# Day0_Samuel_Siahaan_13214088.net
KiCad netlist of a schematic drawn in EAGLE
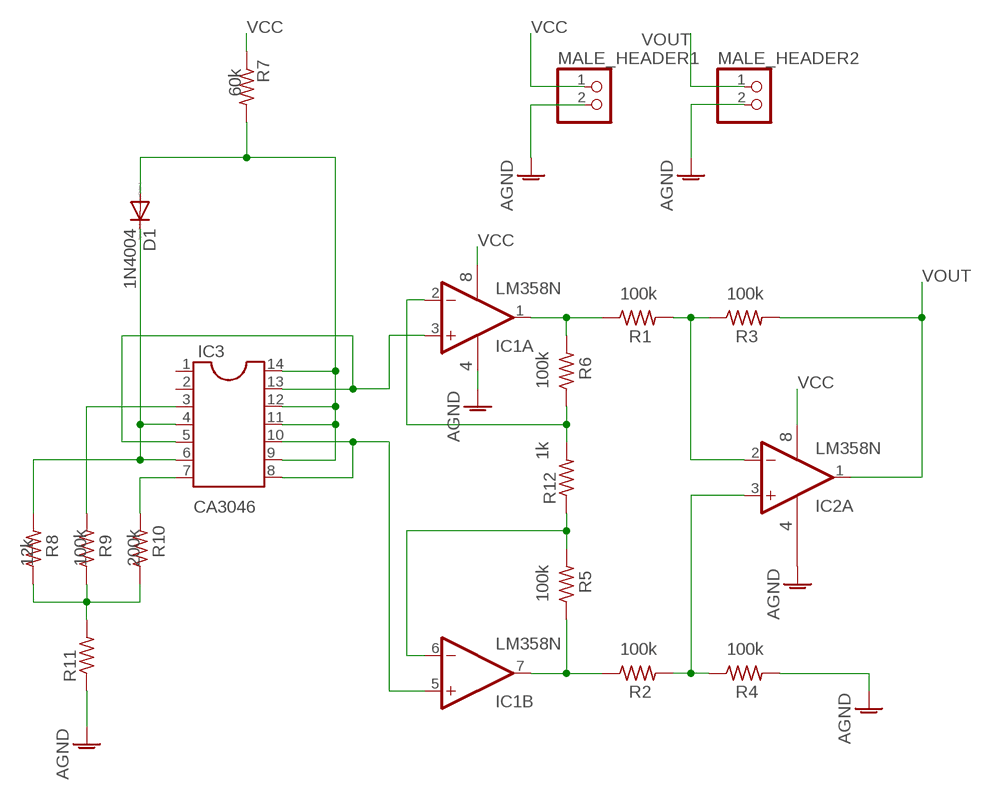
[diagram p0: schematic, sheet 1]

(export (version "E")
  (design (tool "Eeschema 10.0.6"))
  (components
    (comp (ref "D1")
      (value "1N4004")
      (footprint "eagle-import:DO41-10")
      (libsource (lib "eagle-import") (part "1N4004"))
    )
    (comp (ref "IC1")
      (value "LM358N")
      (footprint "eagle-import:DIL08")
      (fields (field (name "PIN4") "4") (field (name "PIN8") "8"))
      (libsource (lib "eagle-import") (part "LM358N"))
    )
    (comp (ref "IC2")
      (value "LM358N")
      (footprint "eagle-import:DIL08")
      (fields (field (name "PIN4") "4") (field (name "PIN8") "8"))
      (libsource (lib "eagle-import") (part "LM358N"))
    )
    (comp (ref "IC3")
      (value "DIL14")
      (footprint "eagle-import:DIL14")
      (fields (field (name "NAMA") "CA3046"))
      (libsource (lib "eagle-import") (part "DIL14"))
    )
    (comp (ref "MALE_HEADER1")
      (value "PINHD-1X2")
      (footprint "eagle-import:1X02")
      (libsource (lib "eagle-import") (part "PINHD-1X2"))
    )
    (comp (ref "MALE_HEADER2")
      (value "PINHD-1X2")
      (footprint "eagle-import:1X02")
      (libsource (lib "eagle-import") (part "PINHD-1X2"))
    )
    (comp (ref "R1")
      (value "R-US_0204/7")
      (footprint "eagle-import:0204_7")
      (fields (field (name "R") "100k"))
      (libsource (lib "eagle-import") (part "R-US_0204/7"))
    )
    (comp (ref "R2")
      (value "R-US_0204/7")
      (footprint "eagle-import:0204_7")
      (fields (field (name "R") "100k"))
      (libsource (lib "eagle-import") (part "R-US_0204/7"))
    )
    (comp (ref "R3")
      (value "R-US_0204/7")
      (footprint "eagle-import:0204_7")
      (fields (field (name "R") "100k"))
      (libsource (lib "eagle-import") (part "R-US_0204/7"))
    )
    (comp (ref "R4")
      (value "R-US_0204/7")
      (footprint "eagle-import:0204_7")
      (fields (field (name "R") "100k"))
      (libsource (lib "eagle-import") (part "R-US_0204/7"))
    )
    (comp (ref "R5")
      (value "R-US_0204/7")
      (footprint "eagle-import:0204_7")
      (fields (field (name "R") "100k"))
      (libsource (lib "eagle-import") (part "R-US_0204/7"))
    )
    (comp (ref "R6")
      (value "R-US_0204/7")
      (footprint "eagle-import:0204_7")
      (fields (field (name "R") "100k"))
      (libsource (lib "eagle-import") (part "R-US_0204/7"))
    )
    (comp (ref "R7")
      (value "R-US_0204/7")
      (footprint "eagle-import:0204_7")
      (fields (field (name "R") "60k"))
      (libsource (lib "eagle-import") (part "R-US_0204/7"))
    )
    (comp (ref "R8")
      (value "R-US_0204/7")
      (footprint "eagle-import:0204_7")
      (fields (field (name "R") "12k"))
      (libsource (lib "eagle-import") (part "R-US_0204/7"))
    )
    (comp (ref "R9")
      (value "R-US_0204/7")
      (footprint "eagle-import:0204_7")
      (fields (field (name "R") "100k"))
      (libsource (lib "eagle-import") (part "R-US_0204/7"))
    )
    (comp (ref "R10")
      (value "R-US_0204/7")
      (footprint "eagle-import:0204_7")
      (fields (field (name "R") "200k"))
      (libsource (lib "eagle-import") (part "R-US_0204/7"))
    )
    (comp (ref "R11")
      (value "R-US_0204/7")
      (footprint "eagle-import:0204_7")
      (libsource (lib "eagle-import") (part "R-US_0204/7"))
    )
    (comp (ref "R12")
      (value "R-US_0204/7")
      (footprint "eagle-import:0204_7")
      (fields (field (name "R") "1k"))
      (libsource (lib "eagle-import") (part "R-US_0204/7"))
    )
  )
  (nets
    (net (code "1") (name "/VCC") (class "Default")
      (node (ref "MALE_HEADER1") (pin "1") (pinfunction "1_1") (pintype "passive"))
      (node (ref "R7") (pin "1") (pinfunction "1_1") (pintype "passive"))
    )
    (net (code "2") (name "/VOUT") (class "Default")
      (node (ref "IC2") (pin "1") (pinfunction "OUT_1") (pintype "output"))
      (node (ref "MALE_HEADER2") (pin "1") (pinfunction "1_1") (pintype "passive"))
      (node (ref "R3") (pin "2") (pinfunction "2_2") (pintype "passive"))
    )
    (net (code "3") (name "AGND") (class "Default")
      (node (ref "MALE_HEADER1") (pin "2") (pinfunction "2_2") (pintype "passive"))
      (node (ref "MALE_HEADER2") (pin "2") (pinfunction "2_2") (pintype "passive"))
      (node (ref "R11") (pin "1") (pinfunction "1_1") (pintype "passive"))
      (node (ref "R4") (pin "2") (pinfunction "2_2") (pintype "passive"))
    )
    (net (code "4") (name "Net-(D1-PadA)") (class "Default")
      (node (ref "D1") (pin "A") (pinfunction "A_A") (pintype "passive"))
      (node (ref "IC3") (pin "11") (pinfunction "11_11") (pintype "passive"))
      (node (ref "IC3") (pin "12") (pinfunction "12_12") (pintype "passive"))
      (node (ref "IC3") (pin "14") (pinfunction "14_14") (pintype "passive"))
      (node (ref "IC3") (pin "9") (pinfunction "9_9") (pintype "passive"))
      (node (ref "R7") (pin "2") (pinfunction "2_2") (pintype "passive"))
    )
    (net (code "5") (name "Net-(D1-PadC)") (class "Default")
      (node (ref "D1") (pin "C") (pinfunction "C_C") (pintype "passive"))
      (node (ref "IC3") (pin "4") (pinfunction "4_4") (pintype "passive"))
      (node (ref "IC3") (pin "6") (pinfunction "6_6") (pintype "passive"))
      (node (ref "R8") (pin "2") (pinfunction "2_2") (pintype "passive"))
    )
    (net (code "6") (name "Net-(IC1A-+IN)") (class "Default")
      (node (ref "IC1") (pin "3") (pinfunction "+IN_3") (pintype "input"))
      (node (ref "IC3") (pin "13") (pinfunction "13_13") (pintype "passive"))
      (node (ref "IC3") (pin "5") (pinfunction "5_5") (pintype "passive"))
    )
    (net (code "7") (name "Net-(IC1A--IN)") (class "Default")
      (node (ref "IC1") (pin "2") (pinfunction "-IN_2") (pintype "input"))
      (node (ref "R12") (pin "2") (pinfunction "2_2") (pintype "passive"))
      (node (ref "R6") (pin "1") (pinfunction "1_1") (pintype "passive"))
    )
    (net (code "8") (name "Net-(IC1A-OUT)") (class "Default")
      (node (ref "IC1") (pin "1") (pinfunction "OUT_1") (pintype "output"))
      (node (ref "R1") (pin "1") (pinfunction "1_1") (pintype "passive"))
      (node (ref "R6") (pin "2") (pinfunction "2_2") (pintype "passive"))
    )
    (net (code "9") (name "Net-(IC1B-+IN)") (class "Default")
      (node (ref "IC1") (pin "5") (pinfunction "+IN_5") (pintype "input"))
      (node (ref "IC3") (pin "10") (pinfunction "10_10") (pintype "passive"))
      (node (ref "IC3") (pin "8") (pinfunction "8_8") (pintype "passive"))
    )
    (net (code "10") (name "Net-(IC1B--IN)") (class "Default")
      (node (ref "IC1") (pin "6") (pinfunction "-IN_6") (pintype "input"))
      (node (ref "R12") (pin "1") (pinfunction "1_1") (pintype "passive"))
      (node (ref "R5") (pin "2") (pinfunction "2_2") (pintype "passive"))
    )
    (net (code "11") (name "Net-(IC1B-OUT)") (class "Default")
      (node (ref "IC1") (pin "7") (pinfunction "OUT_7") (pintype "output"))
      (node (ref "R2") (pin "1") (pinfunction "1_1") (pintype "passive"))
      (node (ref "R5") (pin "1") (pinfunction "1_1") (pintype "passive"))
    )
    (net (code "12") (name "Net-(IC2A-+IN)") (class "Default")
      (node (ref "IC2") (pin "3") (pinfunction "+IN_3") (pintype "input"))
      (node (ref "R2") (pin "2") (pinfunction "2_2") (pintype "passive"))
      (node (ref "R4") (pin "1") (pinfunction "1_1") (pintype "passive"))
    )
    (net (code "13") (name "Net-(IC2A--IN)") (class "Default")
      (node (ref "IC2") (pin "2") (pinfunction "-IN_2") (pintype "input"))
      (node (ref "R1") (pin "2") (pinfunction "2_2") (pintype "passive"))
      (node (ref "R3") (pin "1") (pinfunction "1_1") (pintype "passive"))
    )
    (net (code "14") (name "Net-(IC3-Pad3)") (class "Default")
      (node (ref "IC3") (pin "3") (pinfunction "3_3") (pintype "passive"))
      (node (ref "R9") (pin "2") (pinfunction "2_2") (pintype "passive"))
    )
    (net (code "15") (name "Net-(IC3-Pad7)") (class "Default")
      (node (ref "IC3") (pin "7") (pinfunction "7_7") (pintype "passive"))
      (node (ref "R10") (pin "2") (pinfunction "2_2") (pintype "passive"))
    )
    (net (code "16") (name "Net-(R10-Pad1)") (class "Default")
      (node (ref "R10") (pin "1") (pinfunction "1_1") (pintype "passive"))
      (node (ref "R11") (pin "2") (pinfunction "2_2") (pintype "passive"))
      (node (ref "R8") (pin "1") (pinfunction "1_1") (pintype "passive"))
      (node (ref "R9") (pin "1") (pinfunction "1_1") (pintype "passive"))
    )
    (net (code "17") (name "unconnected-(IC3-Pad1)") (class "Default")
      (node (ref "IC3") (pin "1") (pinfunction "1_1") (pintype "passive"))
    )
    (net (code "18") (name "unconnected-(IC3-Pad2)") (class "Default")
      (node (ref "IC3") (pin "2") (pinfunction "2_2") (pintype "passive"))
    )
  )
)
